# SCH_Hack-Club-PCB_2024-10-30.net
KiCad netlist of a schematic drawn in EasyEDA
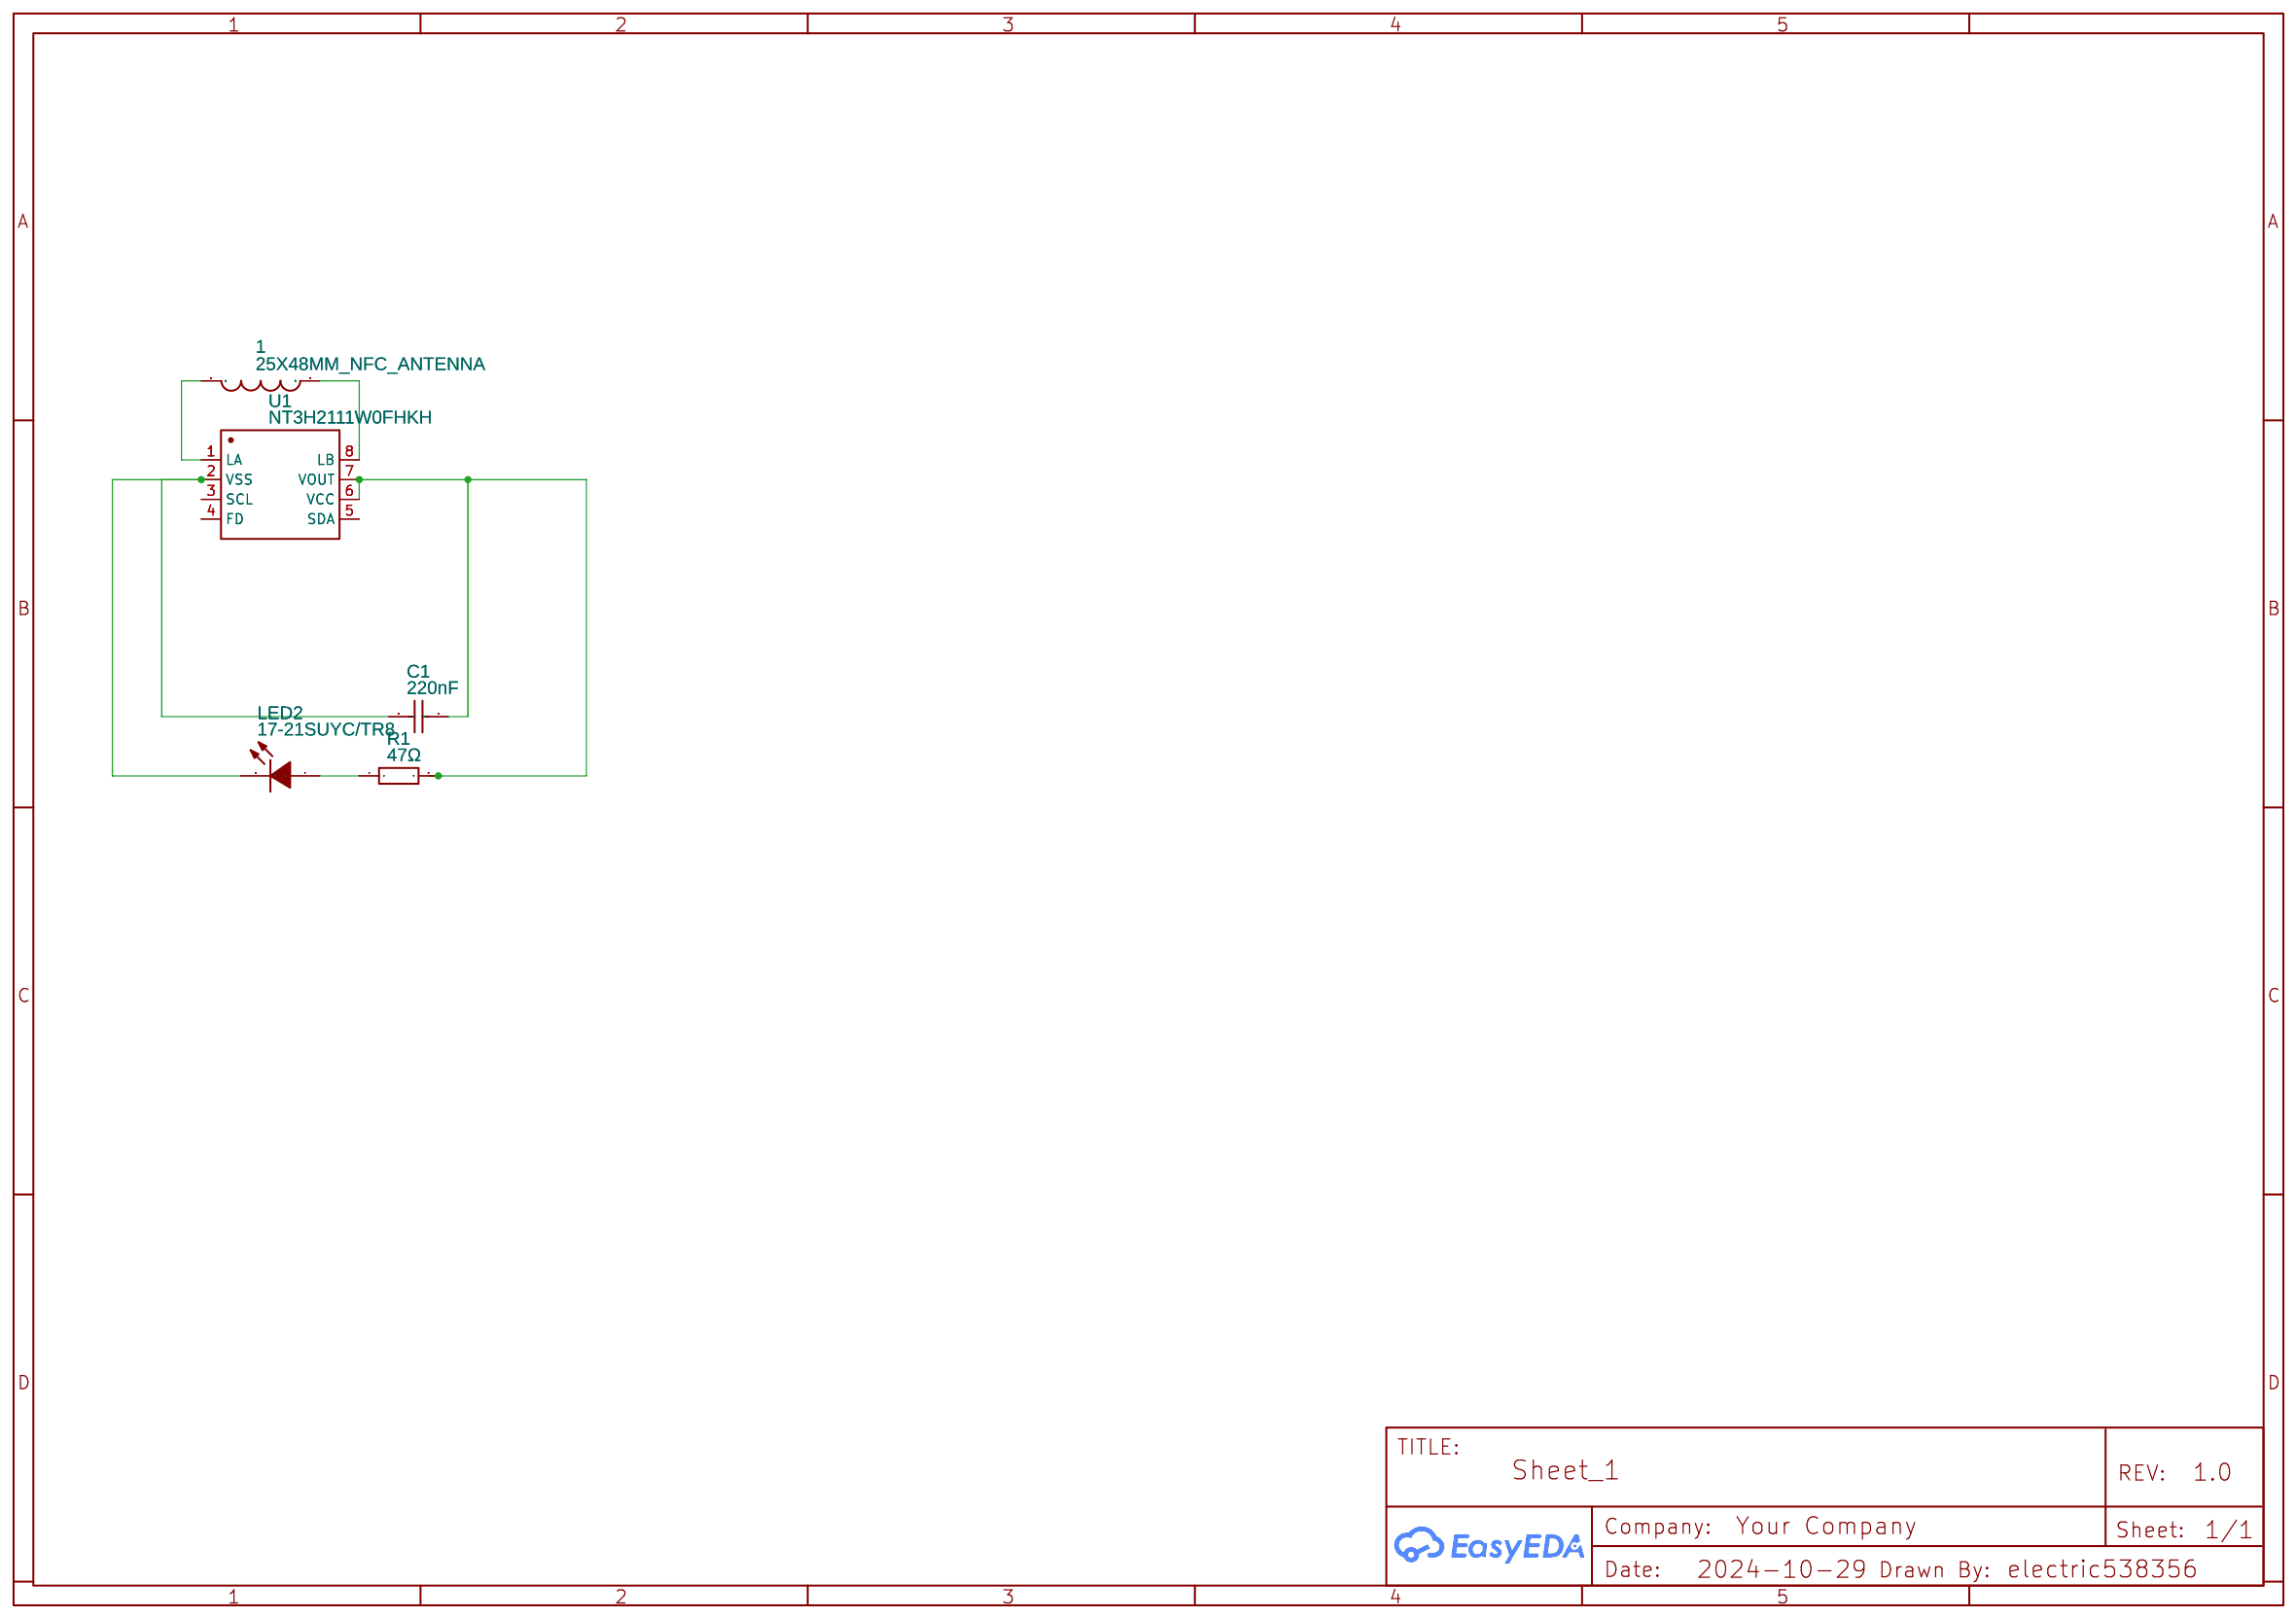
[diagram p0: schematic sheet]

(export (version "E")
  (design (tool "Eeschema 10.0.6"))
  (components
    (comp (ref "1") (value "25X48MM_NFC_ANTENNA") (libsource (lib "") (part "25X48MM_NFC_ANTENNA")))
    (comp (ref "C1")
      (value "220nF")
      (fields
        (field (name "Manufacturer Part") "CL10B224KA8NNNC")
        (field (name "Manufacturer") "SAMSUNG(三星)")
      )
      (libsource (lib "") (part "CL10B224KA8NNNC"))
    )
    (comp (ref "LED2")
      (value "17-21SUYC/TR8")
      (fields (field (name "Manufacturer Part") "KT-0805黄灯") (field (name "Manufacturer") "KENTO"))
      (libsource (lib "") (part "17-21SUYC/TR8"))
    )
    (comp (ref "R1")
      (value "47Ω")
      (fields
        (field (name "Manufacturer Part") "0603WAF470JT5E")
        (field (name "Manufacturer") "UNI-ROYAL(厚声)")
      )
      (libsource (lib "") (part "0603WAF470JT5E"))
    )
    (comp (ref "U1")
      (value "NT3H2111W0FHKH")
      (fields (field (name "Manufacturer") "NXP(恩智浦)"))
      (libsource (lib "") (part "NT3H2111W0FHKH"))
    )
  )
  (nets
    (net (code "1") (name "Net-(LED2-+)") (class "Default")
      (node (ref "LED2") (pin "1") (pinfunction "+_1") (pintype "unspecified"))
      (node (ref "R1") (pin "1") (pinfunction "1_1") (pintype "input"))
    )
    (net (code "2") (name "Net-(LED2--)") (class "Default")
      (node (ref "C1") (pin "1") (pinfunction "1_1") (pintype "input"))
      (node (ref "LED2") (pin "2") (pinfunction "-_2") (pintype "unspecified"))
      (node (ref "U1") (pin "2") (pinfunction "VSS_2") (pintype "unspecified"))
    )
    (net (code "3") (name "Net-(U1-LA)") (class "Default")
      (node (ref "1") (pin "P$2") (pinfunction "P$2_P$2") (pintype "bidirectional"))
      (node (ref "U1") (pin "1") (pinfunction "LA_1") (pintype "unspecified"))
    )
    (net (code "4") (name "Net-(U1-LB)") (class "Default")
      (node (ref "1") (pin "P$1") (pinfunction "P$1_P$1") (pintype "bidirectional"))
      (node (ref "U1") (pin "8") (pinfunction "LB_8") (pintype "unspecified"))
    )
    (net (code "5") (name "Net-(U1-VCC)") (class "Default")
      (node (ref "C1") (pin "2") (pinfunction "2_2") (pintype "input"))
      (node (ref "R1") (pin "2") (pinfunction "2_2") (pintype "input"))
      (node (ref "U1") (pin "6") (pinfunction "VCC_6") (pintype "unspecified"))
      (node (ref "U1") (pin "7") (pinfunction "VOUT_7") (pintype "unspecified"))
    )
    (net (code "6") (name "unconnected-(U1-FD-Pad4)") (class "Default")
      (node (ref "U1") (pin "4") (pinfunction "FD_4") (pintype "unspecified"))
    )
    (net (code "7") (name "unconnected-(U1-SCL-Pad3)") (class "Default")
      (node (ref "U1") (pin "3") (pinfunction "SCL_3") (pintype "unspecified"))
    )
    (net (code "8") (name "unconnected-(U1-SDA-Pad5)") (class "Default")
      (node (ref "U1") (pin "5") (pinfunction "SDA_5") (pintype "unspecified"))
    )
  )
)
